# controller_schematic.net
KiCad netlist of a schematic drawn in EAGLE
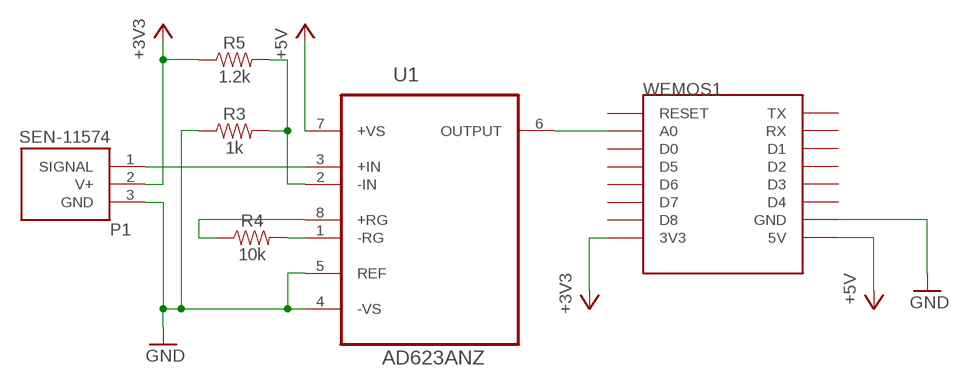
[diagram p0: schematic, sheet 1]

(export (version "E")
  (design (tool "Eeschema 10.0.6"))
  (components
    (comp (ref "P1")
      (value "SEN-11574")
      (footprint "eagle-import:XDCR_SEN-11574")
      (fields (field (name "MF") "SparkFun"))
      (libsource (lib "eagle-import") (part "SEN-11574"))
    )
    (comp (ref "R3")
      (value "1k")
      (footprint "eagle-import:AXIAL-0.3")
      (libsource (lib "eagle-import") (part "1KOHM-HORIZ-1/4W-5%"))
    )
    (comp (ref "R4")
      (value "10k")
      (footprint "eagle-import:AXIAL-0.3")
      (libsource (lib "eagle-import") (part "10KOHM-HORIZ-1/4W-1%"))
    )
    (comp (ref "R5")
      (value "1.2k")
      (footprint "eagle-import:AXIAL-0.3")
      (libsource (lib "eagle-import") (part "1KOHM-HORIZ-1/4W-1%"))
    )
    (comp (ref "U1")
      (value "AD623ANZ")
      (footprint "eagle-import:DIP254P762X533-8")
      (fields (field (name "MF") "Analog Devices") (field (name "SPICEPREFIX") "X"))
      (libsource (lib "eagle-import") (part "AD623ANZ"))
    )
    (comp (ref "WEMOS1")
      (value "WEMOS-D1-MINI")
      (footprint "eagle-import:WEMOS-D1-MINI")
      (libsource (lib "eagle-import") (part "WEMOS-D1-MINI"))
    )
  )
  (nets
    (net (code "1") (name "+3V3") (class "Default")
      (node (ref "P1") (pin "2") (pinfunction "V+_2") (pintype "power_in"))
      (node (ref "R5") (pin "P$1") (pinfunction "1_P$1") (pintype "passive"))
      (node (ref "WEMOS1") (pin "3V3") (pinfunction "3V3_3V3") (pintype "bidirectional"))
    )
    (net (code "2") (name "+5V") (class "Default")
      (node (ref "U1") (pin "7") (pinfunction "+VS_7") (pintype "power_in"))
      (node (ref "WEMOS1") (pin "5V") (pinfunction "5V_5V") (pintype "bidirectional"))
    )
    (net (code "3") (name "GND") (class "Default")
      (node (ref "P1") (pin "3") (pinfunction "GND_3") (pintype "power_in"))
      (node (ref "R3") (pin "P$1") (pinfunction "1_P$1") (pintype "passive"))
      (node (ref "U1") (pin "4") (pinfunction "-VS_4") (pintype "power_in"))
      (node (ref "U1") (pin "5") (pinfunction "REF_5") (pintype "passive"))
      (node (ref "WEMOS1") (pin "GND") (pinfunction "GND_GND") (pintype "bidirectional"))
    )
    (net (code "4") (name "Net-(P1-SIGNAL)") (class "Default")
      (node (ref "P1") (pin "1") (pinfunction "SIGNAL_1") (pintype "bidirectional"))
      (node (ref "U1") (pin "3") (pinfunction "+IN_3") (pintype "input"))
    )
    (net (code "5") (name "Net-(R3-2)") (class "Default")
      (node (ref "R3") (pin "P$2") (pinfunction "2_P$2") (pintype "passive"))
      (node (ref "R5") (pin "P$2") (pinfunction "2_P$2") (pintype "passive"))
      (node (ref "U1") (pin "2") (pinfunction "-IN_2") (pintype "input"))
    )
    (net (code "6") (name "Net-(R4-1)") (class "Default")
      (node (ref "R4") (pin "P$1") (pinfunction "1_P$1") (pintype "passive"))
      (node (ref "U1") (pin "8") (pinfunction "+RG_8") (pintype "passive"))
    )
    (net (code "7") (name "Net-(R4-2)") (class "Default")
      (node (ref "R4") (pin "P$2") (pinfunction "2_P$2") (pintype "passive"))
      (node (ref "U1") (pin "1") (pinfunction "-RG_1") (pintype "passive"))
    )
    (net (code "8") (name "Net-(U1-OUTPUT)") (class "Default")
      (node (ref "U1") (pin "6") (pinfunction "OUTPUT_6") (pintype "output"))
      (node (ref "WEMOS1") (pin "A0") (pinfunction "A0_A0") (pintype "bidirectional"))
    )
    (net (code "9") (name "unconnected-(WEMOS1-PadD0)") (class "Default")
      (node (ref "WEMOS1") (pin "D0") (pinfunction "D0_D0") (pintype "bidirectional"))
    )
    (net (code "10") (name "unconnected-(WEMOS1-PadD1)") (class "Default")
      (node (ref "WEMOS1") (pin "D1") (pinfunction "D1_D1") (pintype "bidirectional"))
    )
    (net (code "11") (name "unconnected-(WEMOS1-PadD2)") (class "Default")
      (node (ref "WEMOS1") (pin "D2") (pinfunction "D2_D2") (pintype "bidirectional"))
    )
    (net (code "12") (name "unconnected-(WEMOS1-PadD3)") (class "Default")
      (node (ref "WEMOS1") (pin "D3") (pinfunction "D3_D3") (pintype "bidirectional"))
    )
    (net (code "13") (name "unconnected-(WEMOS1-PadD4)") (class "Default")
      (node (ref "WEMOS1") (pin "D4") (pinfunction "D4_D4") (pintype "bidirectional"))
    )
    (net (code "14") (name "unconnected-(WEMOS1-PadD5)") (class "Default")
      (node (ref "WEMOS1") (pin "D5") (pinfunction "D5_D5") (pintype "bidirectional"))
    )
    (net (code "15") (name "unconnected-(WEMOS1-PadD6)") (class "Default")
      (node (ref "WEMOS1") (pin "D6") (pinfunction "D6_D6") (pintype "bidirectional"))
    )
    (net (code "16") (name "unconnected-(WEMOS1-PadD7)") (class "Default")
      (node (ref "WEMOS1") (pin "D7") (pinfunction "D7_D7") (pintype "bidirectional"))
    )
    (net (code "17") (name "unconnected-(WEMOS1-PadD8)") (class "Default")
      (node (ref "WEMOS1") (pin "D8") (pinfunction "D8_D8") (pintype "bidirectional"))
    )
    (net (code "18") (name "unconnected-(WEMOS1-PadRESET)") (class "Default")
      (node (ref "WEMOS1") (pin "RESET") (pinfunction "RESET_RESET") (pintype "bidirectional"))
    )
    (net (code "19") (name "unconnected-(WEMOS1-PadRX)") (class "Default")
      (node (ref "WEMOS1") (pin "RX") (pinfunction "RX_RX") (pintype "bidirectional"))
    )
    (net (code "20") (name "unconnected-(WEMOS1-PadTX)") (class "Default")
      (node (ref "WEMOS1") (pin "TX") (pinfunction "TX_TX") (pintype "bidirectional"))
    )
  )
)
